# FC_board.net
KiCad netlist of a schematic drawn in Altium Designer
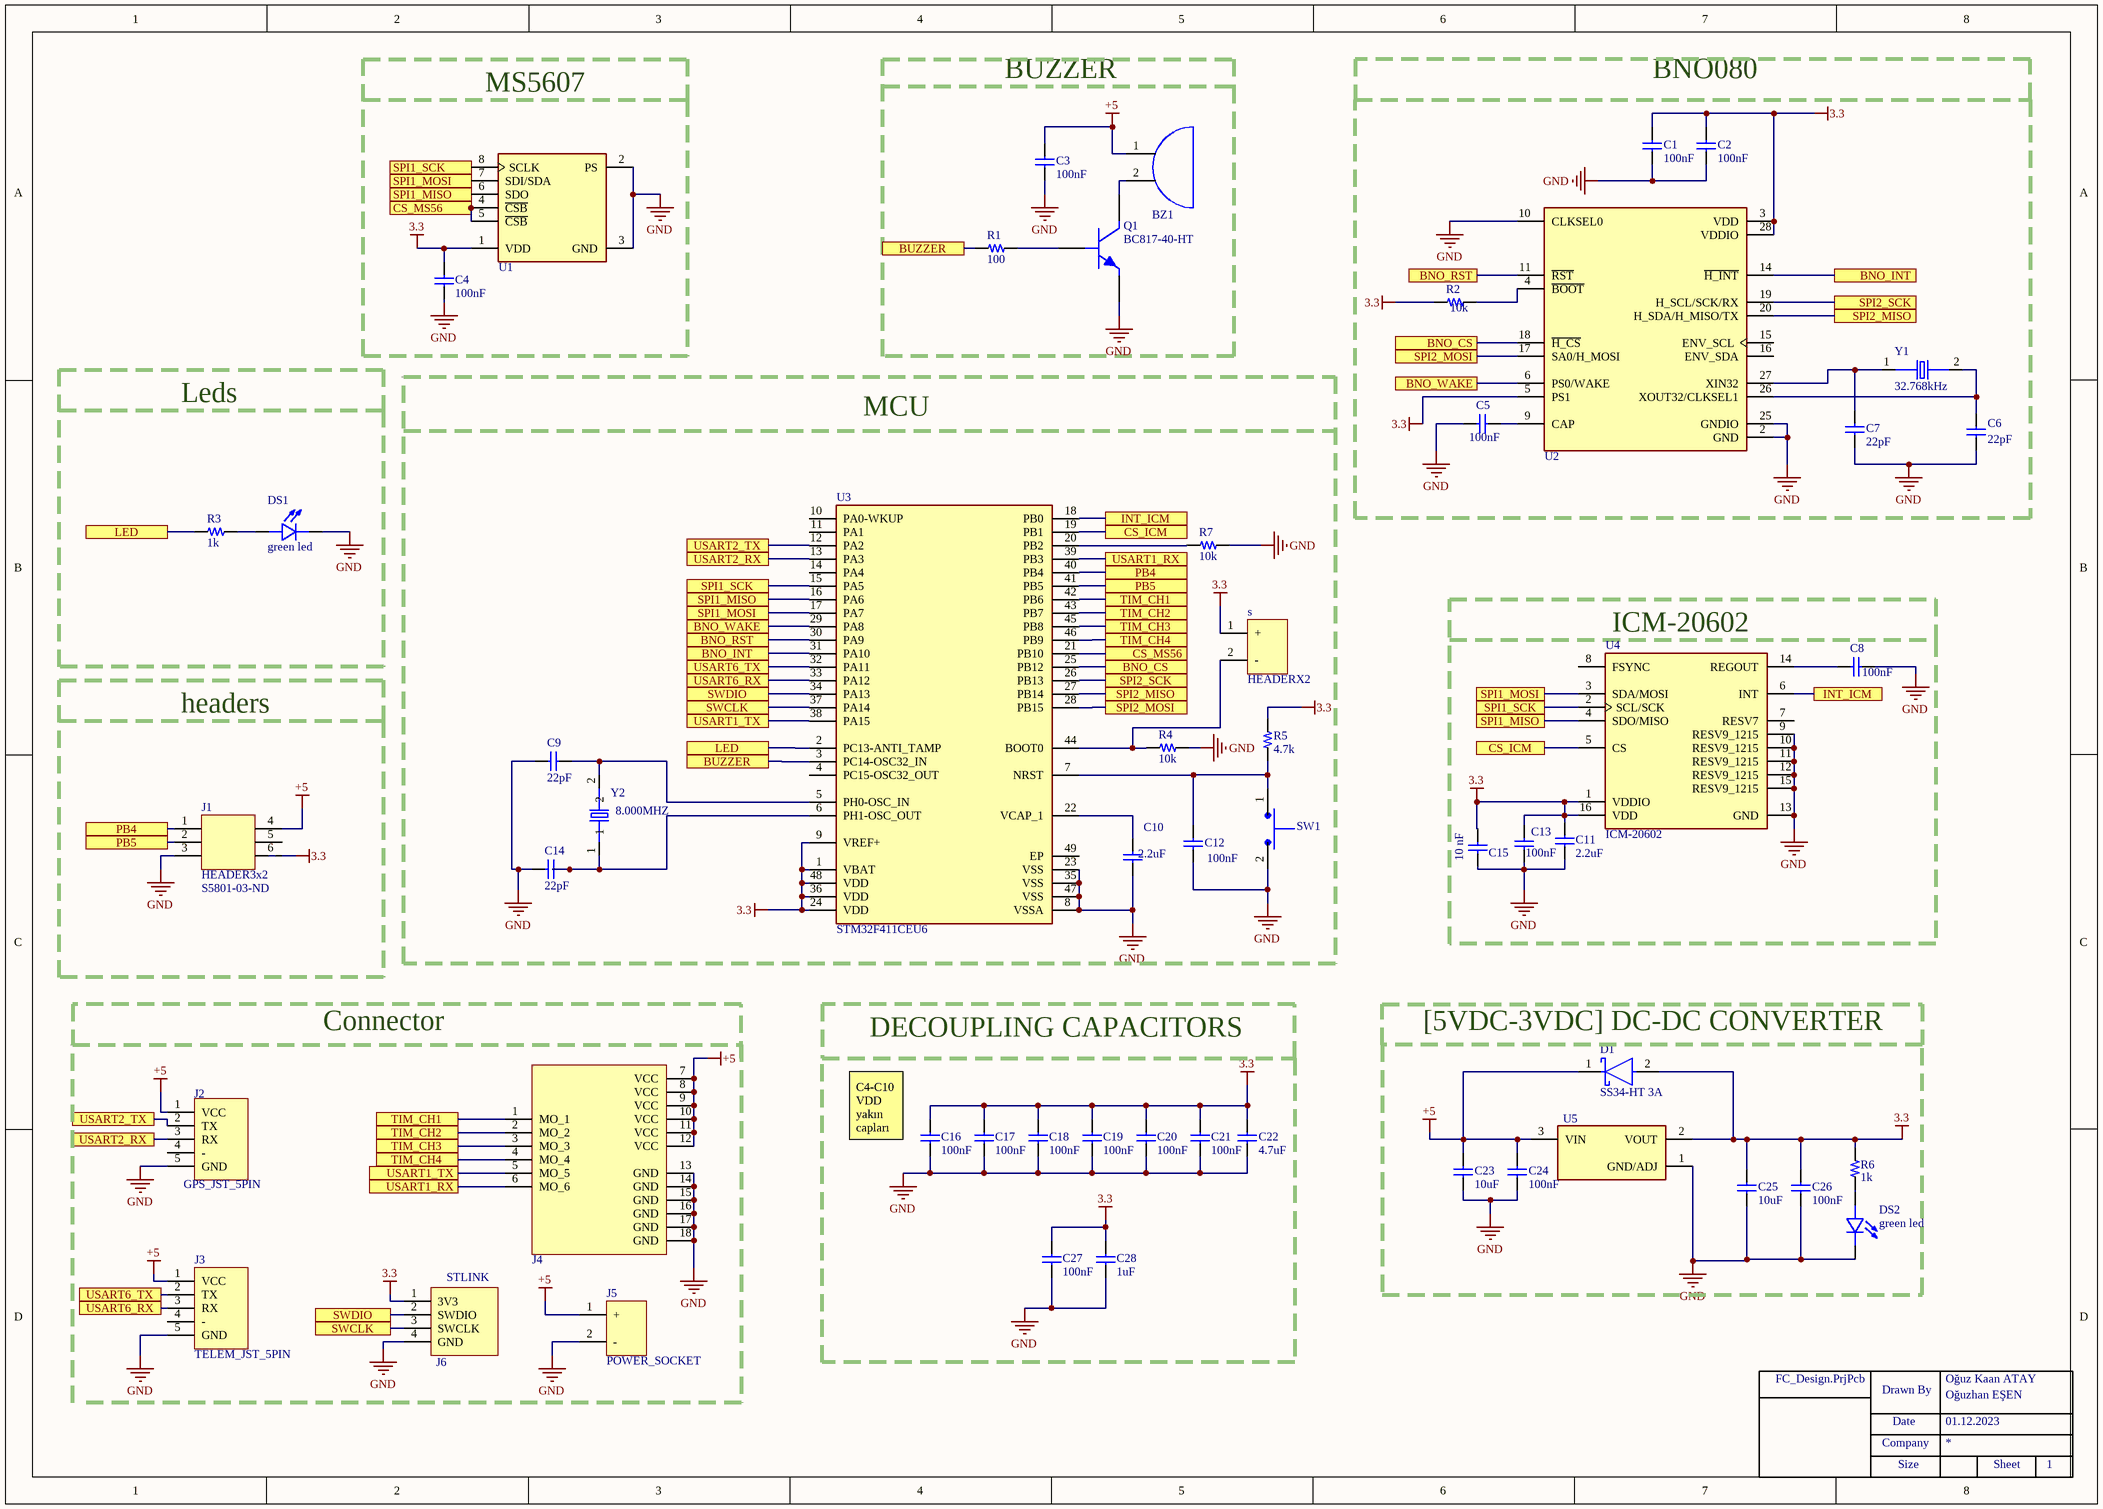
[diagram p0: FC_board.SchDoc]

(export (version "E")
  (design (tool "Eeschema 10.0.6"))
  (components
    (comp (ref "BZ1")
      (value "MB9650B05NP")
      (footprint "BUZZER")
      (libsource (lib "FC_Design_LIBINT") (part "MB9650B05NP"))
    )
    (comp (ref "C1")
      (value "CL21B105KBFNNNE")
      (footprint "CAP_0805")
      (description "CAP CER 1UF 50V X7R 0805")
      (fields
        (field (name "MANUFACTURER") "Samsung")
        (field (name "TOLERANCE") "10%")
        (field (name "CAPACITANCE") "100nF")
        (field (name "DESIGNED BY") "Oğuzhan EŞEN")
      )
      (libsource (lib "FC_Design_LIBINT") (part "CAP CER 1uF 0805"))
    )
    (comp (ref "C2")
      (value "CL21B105KBFNNNE")
      (footprint "CAP_0805")
      (description "CAP CER 1UF 50V X7R 0805")
      (fields
        (field (name "MANUFACTURER") "Samsung")
        (field (name "TOLERANCE") "10%")
        (field (name "CAPACITANCE") "100nF")
        (field (name "DESIGNED BY") "Oğuzhan EŞEN")
      )
      (libsource (lib "FC_Design_LIBINT") (part "CAP CER 1uF 0805"))
    )
    (comp (ref "C3")
      (value "CAP CER 100nF 0805")
      (footprint "CAP_0805")
      (description "CAP CER 100nF 50V X7R 0805")
      (fields
        (field (name "MANUFACTURER") "Samsung")
        (field (name "MANUFACTURER PART NUMBER") "CL21B105KBFNNNE")
        (field (name "CAPACITANCE") "100nF")
        (field (name "DESIGNED BY") "Oğuzhan EŞEN")
      )
      (libsource (lib "FC_Design_LIBINT") (part "CAP CER 100nF 0805"))
    )
    (comp (ref "C4")
      (value "CAP CER 100nF 0805")
      (footprint "CAP_0805")
      (description "CAP CER 100nF 50V X7R 0805")
      (fields
        (field (name "MANUFACTURER") "Samsung")
        (field (name "MANUFACTURER PART NUMBER") "CL21B105KBFNNNE")
        (field (name "CAPACITANCE") "100nF")
        (field (name "DESIGNED BY") "Oğuzhan EŞEN")
      )
      (libsource (lib "FC_Design_LIBINT") (part "CAP CER 100nF 0805"))
    )
    (comp (ref "C5")
      (value "CAP CER  0.1uF 0805")
      (footprint "CAP_0805")
      (description "CAP CER  0.1UF 50V X7R 0805")
      (fields
        (field (name "MANUFACTURER") "Samsung")
        (field (name "MANUFACTURER PART NUMBER") "CL21B105KBFNNNE")
        (field (name "CAPACITANCE") "100nF")
        (field (name "DESIGNED BY") "Oğuzhan EŞEN")
      )
      (libsource (lib "FC_Design_LIBINT") (part "CAP CER  0.1uF 0805"))
    )
    (comp (ref "C6")
      (value "CL21B105KBFNNNE")
      (footprint "CAP_0805")
      (description "CAP CER 22pF 50V X7R 0805")
      (fields
        (field (name "MANUFACTURER") "Samsung")
        (field (name "TOLERANCE") "10%")
        (field (name "CAPACITANCE") "22pF")
        (field (name "DESIGNED BY") "Oğuzhan EŞEN")
      )
      (libsource (lib "FC_Design_LIBINT") (part "CAP CER 22pF 0805"))
    )
    (comp (ref "C7")
      (value "CL21B105KBFNNNE")
      (footprint "CAP_0805")
      (description "CAP CER 22pF 50V X7R 0805")
      (fields
        (field (name "MANUFACTURER") "Samsung")
        (field (name "TOLERANCE") "10%")
        (field (name "CAPACITANCE") "22pF")
        (field (name "DESIGNED BY") "Oğuzhan EŞEN")
      )
      (libsource (lib "FC_Design_LIBINT") (part "CAP CER 22pF 0805"))
    )
    (comp (ref "C8")
      (value "CAP CER  0.1uF 0805")
      (footprint "CAP_0805")
      (description "CAP CER  0.1UF 50V X7R 0805")
      (fields
        (field (name "MANUFACTURER") "Samsung")
        (field (name "MANUFACTURER PART NUMBER") "CL21B105KBFNNNE")
        (field (name "CAPACITANCE") "100nF")
        (field (name "DESIGNED BY") "Oğuzhan EŞEN")
      )
      (libsource (lib "FC_Design_LIBINT") (part "CAP CER  0.1uF 0805"))
    )
    (comp (ref "C9")
      (value "CL21B105KBFNNNE")
      (footprint "CAP_0805")
      (description "CAP CER 22pF 50V X7R 0805")
      (fields
        (field (name "MANUFACTURER") "Samsung")
        (field (name "TOLERANCE") "10%")
        (field (name "CAPACITANCE") "22pF")
        (field (name "DESIGNED BY") "Oğuzhan EŞEN")
      )
      (libsource (lib "FC_Design_LIBINT") (part "CAP CER 22pF 0805"))
    )
    (comp (ref "C10")
      (value "CL21B105KBFNNNE")
      (footprint "CAP_0805")
      (description "CAP CER 22pF 50V X7R 0805")
      (fields
        (field (name "MANUFACTURER") "Samsung")
        (field (name "TOLERANCE") "10%")
        (field (name "CAPACITANCE") "2.2uF")
        (field (name "DESIGNED BY") "Oğuzhan EŞEN")
      )
      (libsource (lib "FC_Design_LIBINT") (part "CAP CER 22pF 0805"))
    )
    (comp (ref "C11")
      (value "CL21A475KAQNNNE")
      (footprint "CAP_0805")
      (description "CAP CER  2.2UF 50V X7R 0805")
      (fields
        (field (name "MANUFACTURER") "Samsung")
        (field (name "TOLERANCE") "10%")
        (field (name "CAPACITANCE") "2.2uF")
        (field (name "DESIGNED BY") "Oğuzhan EŞEN")
      )
      (libsource (lib "FC_Design_LIBINT") (part "CAP CER 2.2uF 0805_1"))
    )
    (comp (ref "C12")
      (value "~")
      (footprint "CAP_0805")
      (description "CAP CER  0.1UF 50V X7R 0805")
      (fields
        (field (name "MANUFACTURER") "Samsung")
        (field (name "MANUFACTURER PART NUMBER") "CL21B105KBFNNNE")
        (field (name "CAPACITANCE") "100nF")
        (field (name "DESIGNED BY") "Oğuzhan EŞEN")
      )
      (libsource (lib "FC_Design_LIBINT") (part "CAP CER  0.1uF 0805"))
    )
    (comp (ref "C13")
      (value "CAP CER  0.1uF 0805")
      (footprint "CAP_0805")
      (description "CAP CER  0.1UF 50V X7R 0805")
      (fields
        (field (name "MANUFACTURER") "Samsung")
        (field (name "MANUFACTURER PART NUMBER") "CL21B105KBFNNNE")
        (field (name "CAPACITANCE") "100nF")
        (field (name "DESIGNED BY") "Oğuzhan EŞEN")
      )
      (libsource (lib "FC_Design_LIBINT") (part "CAP CER  0.1uF 0805"))
    )
    (comp (ref "C14")
      (value "CL21B105KBFNNNE")
      (footprint "CAP_0805")
      (description "CAP CER 22pF 50V X7R 0805")
      (fields
        (field (name "MANUFACTURER") "Samsung")
        (field (name "TOLERANCE") "10%")
        (field (name "CAPACITANCE") "22pF")
        (field (name "DESIGNED BY") "Oğuzhan EŞEN")
      )
      (libsource (lib "FC_Design_LIBINT") (part "CAP CER 22pF 0805"))
    )
    (comp (ref "C15")
      (value "CAP CER 10nF 0805")
      (footprint "CAP_0805")
      (description "CAP CER  10nF 50V X7R 0805")
      (libsource (lib "FC_Design_LIBINT") (part "CAP CER 10nF 0805"))
    )
    (comp (ref "C16")
      (value "~")
      (footprint "CAP_0805")
      (description "CAP CER 100pF 50V X7R 0805")
      (fields
        (field (name "MANUFACTURER") "Samsung")
        (field (name "MANUFACTURER PART NUMBER") "CL21B105KBFNNNE")
        (field (name "CAPACITANCE") "100nF")
        (field (name "DESIGNED BY") "Oğuzhan EŞEN")
      )
      (libsource (lib "FC_Design_LIBINT") (part "CAP CER 100pF 0805"))
    )
    (comp (ref "C17")
      (value "~")
      (footprint "CAP_0805")
      (description "CAP CER 100pF 50V X7R 0805")
      (fields
        (field (name "MANUFACTURER") "Samsung")
        (field (name "MANUFACTURER PART NUMBER") "CL21B105KBFNNNE")
        (field (name "CAPACITANCE") "100nF")
        (field (name "DESIGNED BY") "Oğuzhan EŞEN")
      )
      (libsource (lib "FC_Design_LIBINT") (part "CAP CER 100pF 0805"))
    )
    (comp (ref "C18")
      (value "~")
      (footprint "CAP_0805")
      (description "CAP CER 100pF 50V X7R 0805")
      (fields
        (field (name "MANUFACTURER") "Samsung")
        (field (name "MANUFACTURER PART NUMBER") "CL21B105KBFNNNE")
        (field (name "CAPACITANCE") "100nF")
        (field (name "DESIGNED BY") "Oğuzhan EŞEN")
      )
      (libsource (lib "FC_Design_LIBINT") (part "CAP CER 100pF 0805"))
    )
    (comp (ref "C19")
      (value "~")
      (footprint "CAP_0805")
      (description "CAP CER 100pF 50V X7R 0805")
      (fields
        (field (name "MANUFACTURER") "Samsung")
        (field (name "MANUFACTURER PART NUMBER") "CL21B105KBFNNNE")
        (field (name "CAPACITANCE") "100nF")
        (field (name "DESIGNED BY") "Oğuzhan EŞEN")
      )
      (libsource (lib "FC_Design_LIBINT") (part "CAP CER 100pF 0805"))
    )
    (comp (ref "C20")
      (value "~")
      (footprint "CAP_0805")
      (description "CAP CER 100pF 50V X7R 0805")
      (fields
        (field (name "MANUFACTURER") "Samsung")
        (field (name "MANUFACTURER PART NUMBER") "CL21B105KBFNNNE")
        (field (name "CAPACITANCE") "100nF")
        (field (name "DESIGNED BY") "Oğuzhan EŞEN")
      )
      (libsource (lib "FC_Design_LIBINT") (part "CAP CER 100pF 0805"))
    )
    (comp (ref "C21")
      (value "~")
      (footprint "CAP_0805")
      (description "CAP CER 100pF 50V X7R 0805")
      (fields
        (field (name "MANUFACTURER") "Samsung")
        (field (name "MANUFACTURER PART NUMBER") "CL21B105KBFNNNE")
        (field (name "CAPACITANCE") "100nF")
        (field (name "DESIGNED BY") "Oğuzhan EŞEN")
      )
      (libsource (lib "FC_Design_LIBINT") (part "CAP CER 100pF 0805"))
    )
    (comp (ref "C22")
      (value "~")
      (footprint "CAP_0805")
      (description "CAP CER 4.7UF 25V X5R 0805")
      (fields
        (field (name "MANUFACTURER") "Samsung")
        (field (name "MANUFACTURER PART NUMBER") "CL21A475KAQNNNE")
        (field (name "CAPACITANCE") "4.7uF")
        (field (name "DESIGNED BY") "Oğuzhan EŞEN")
      )
      (libsource (lib "FC_Design_LIBINT") (part "CAP CER 4,7uF 0805"))
    )
    (comp (ref "C23")
      (value "CAP CER 10uF 0805")
      (footprint "CAP_0805")
      (description "CAP CER 10uF 25V X5R 0805")
      (fields
        (field (name "MANUFACTURER") "Samsung")
        (field (name "MANUFACTURER PART NUMBER") "CL21A475KAQNNNE")
        (field (name "CAPACITANCE") "10uF")
        (field (name "DESIGNED BY") "Oğuzhan EŞEN")
      )
      (libsource (lib "FC_Design_LIBINT") (part "CAP CER 10uF 0805"))
    )
    (comp (ref "C24")
      (value "~")
      (footprint "CAP_0805")
      (description "CAP CER 100nF 50V X7R 0805")
      (fields
        (field (name "MANUFACTURER") "Samsung")
        (field (name "MANUFACTURER PART NUMBER") "CL21B105KBFNNNE")
        (field (name "CAPACITANCE") "100nF")
        (field (name "DESIGNED BY") "Oğuzhan EŞEN")
      )
      (libsource (lib "FC_Design_LIBINT") (part "CAP CER 100nF 0805"))
    )
    (comp (ref "C25")
      (value "CAP CER 10uF 0805")
      (footprint "CAP_0805")
      (description "CAP CER 10uF 25V X5R 0805")
      (fields
        (field (name "MANUFACTURER") "Samsung")
        (field (name "MANUFACTURER PART NUMBER") "CL21A475KAQNNNE")
        (field (name "CAPACITANCE") "10uF")
        (field (name "DESIGNED BY") "Oğuzhan EŞEN")
      )
      (libsource (lib "FC_Design_LIBINT") (part "CAP CER 10uF 0805"))
    )
    (comp (ref "C26")
      (value "~")
      (footprint "CAP_0805")
      (description "CAP CER 100nF 50V X7R 0805")
      (fields
        (field (name "MANUFACTURER") "Samsung")
        (field (name "MANUFACTURER PART NUMBER") "CL21B105KBFNNNE")
        (field (name "CAPACITANCE") "100nF")
        (field (name "DESIGNED BY") "Oğuzhan EŞEN")
      )
      (libsource (lib "FC_Design_LIBINT") (part "CAP CER 100nF 0805"))
    )
    (comp (ref "C27")
      (value "~")
      (footprint "CAP_0805")
      (description "CAP CER 100nF 50V X7R 0805")
      (fields
        (field (name "MANUFACTURER") "Samsung")
        (field (name "MANUFACTURER PART NUMBER") "CL21B105KBFNNNE")
        (field (name "CAPACITANCE") "100nF")
        (field (name "DESIGNED BY") "Oğuzhan EŞEN")
      )
      (libsource (lib "FC_Design_LIBINT") (part "CAP CER 100nF 0805"))
    )
    (comp (ref "C28")
      (value "~")
      (footprint "CAP_0805")
      (description "CAP CER 1UF 50V X7R 0805")
      (fields
        (field (name "MANUFACTURER") "Samsung")
        (field (name "MANUFACTURER PART NUMBER") "CL21B105KBFNNNE")
        (field (name "CAPACITANCE") "1uF")
        (field (name "DESIGNED BY") "Oğuzhan EŞEN")
      )
      (libsource (lib "FC_Design_LIBINT") (part "CAP CER 1uF 0805"))
    )
    (comp (ref "D1")
      (value "SS34-HT 3A")
      (footprint "FP-95402-MFG")
      (description "DIODE SCHOTTKY 40V 3A DIODE SCHOTTKY 40V 3A DO214AB")
      (fields (field (name "MANUFACTURER") "Vishay") (field (name "MANUFACTURER PART NUMBER") "SS34-E3/57T"))
      (libsource (lib "Altium Content Vault") (part "1d6ec82d83fb6aee721767c19dac4b9"))
    )
    (comp (ref "DS1")
      (value "green led")
      (footprint "GREEEN_LED_0805")
      (libsource (lib "FC_Design_LIBINT") (part "green led"))
    )
    (comp (ref "DS2")
      (value "green led")
      (footprint "GREEEN_LED_0805")
      (libsource (lib "") (part "green led_1"))
    )
    (comp (ref "J1")
      (value "HEADER3x2")
      (footprint "HEADER3x2")
      (description "CONN HEADER 2MM DUAL STR 6POS")
      (fields
        (field (name "MANUFACTURER") "Sullins")
        (field (name "MANUFACTURER PART NUMBER") "NRPN032PAEN-RC")
        (field (name "SUPPLIER PART NUMBER 1") "S5801-03-ND")
        (field (name "DESIGNED BY") "Oğuzhan EŞEN")
      )
      (libsource (lib "Arduino") (part "HEADER3x2"))
    )
    (comp (ref "J2")
      (value "GPS_JST_5PIN")
      (footprint "JST_5PIN_125")
      (libsource (lib "FC_Design_LIBINT") (part "GPS_JST_5PIN"))
    )
    (comp (ref "J3")
      (value "TELEM_JST_5PIN")
      (footprint "JST_5PIN_125")
      (libsource (lib "FC_Design_LIBINT") (part "TELEM_JST_5PIN"))
    )
    (comp (ref "J4")
      (value "Motor_Outputs")
      (footprint "MOTORS")
      (libsource (lib "FC_Design_LIBINT") (part "Motor_Outputs"))
    )
    (comp (ref "J5")
      (value "POWER_SOCKET")
      (footprint "JST_2PIN_2.54")
      (libsource (lib "FC_Design_LIBINT") (part "POWER_SOCKET"))
    )
    (comp (ref "J6")
      (value "STLINK")
      (footprint "HEADER_4_MALE")
      (libsource (lib "FC_Design_LIBINT") (part "RECIVER"))
    )
    (comp (ref "Q1")
      (value "BC817-40-HT")
      (footprint "SOT23")
      (description "npn transistor")
      (libsource (lib "FC_Design_LIBINT") (part "BC817-40-HT"))
    )
    (comp (ref "R1")
      (value "100")
      (footprint "RES_0805")
      (description "910 Ohms Â±1% 0.125W, 1/8W Chip Resistor 0805 (2012 Metric) Moisture Resistant Thick Film")
      (fields (field (name "MF") "Yageo") (field (name "MP") "RC0805FR-07910RL"))
      (libsource (lib "FC_Design_LIBINT") (part "RESISTOR_0805"))
    )
    (comp (ref "R2")
      (value "10k")
      (footprint "RES_0805")
      (description "910 Ohms Â±1% 0.125W, 1/8W Chip Resistor 0805 (2012 Metric) Moisture Resistant Thick Film")
      (fields (field (name "MF") "Yageo") (field (name "MP") "RC0805FR-07910RL"))
      (libsource (lib "FC_Design_LIBINT") (part "RESISTOR_0805"))
    )
    (comp (ref "R3")
      (value "1k")
      (footprint "RES_0805")
      (description "910 Ohms Â±1% 0.125W, 1/8W Chip Resistor 0805 (2012 Metric) Moisture Resistant Thick Film")
      (fields (field (name "MF") "Yageo") (field (name "MP") "RC0805FR-07910RL"))
      (libsource (lib "FC_Design_LIBINT") (part "RESISTOR_0805"))
    )
    (comp (ref "R4")
      (value "10k")
      (footprint "RES_0805")
      (description "910 Ohms Â±1% 0.125W, 1/8W Chip Resistor 0805 (2012 Metric) Moisture Resistant Thick Film")
      (fields (field (name "MF") "Yageo") (field (name "MP") "RC0805FR-07910RL"))
      (libsource (lib "FC_Design_LIBINT") (part "RESISTOR_0805"))
    )
    (comp (ref "R5")
      (value "4.7k")
      (footprint "RES_0805")
      (description "910 Ohms Â±1% 0.125W, 1/8W Chip Resistor 0805 (2012 Metric) Moisture Resistant Thick Film")
      (fields (field (name "MF") "Yageo") (field (name "MP") "RC0805FR-07910RL"))
      (libsource (lib "FC_Design_LIBINT") (part "RESISTOR_0805"))
    )
    (comp (ref "R6")
      (value "1k")
      (footprint "RES_0805")
      (description "910 Ohms Â±1% 0.125W, 1/8W Chip Resistor 0805 (2012 Metric) Moisture Resistant Thick Film")
      (fields (field (name "MF") "Yageo") (field (name "MP") "RC0805FR-07910RL"))
      (libsource (lib "FC_Design_LIBINT") (part "RESISTOR_0805"))
    )
    (comp (ref "R7")
      (value "10k")
      (footprint "RES_0805")
      (description "910 Ohms Â±1% 0.125W, 1/8W Chip Resistor 0805 (2012 Metric) Moisture Resistant Thick Film")
      (fields (field (name "MF") "Yageo") (field (name "MP") "RC0805FR-07910RL"))
      (libsource (lib "FC_Design_LIBINT") (part "RESISTOR_0805"))
    )
    (comp (ref "s")
      (value "HEADERX2")
      (footprint "PIN_2.54")
      (libsource (lib "FC_Design_LIBINT") (part "HEADERX2"))
    )
    (comp (ref "SW1")
      (value "Switch Tactile")
      (footprint "BUTTON")
      (description "Switch Tactile N.O. SPST Rectangular Button J-Bend 0.02A 15VDC 5N SMD Embossed Tape and Reel")
      (fields
        (field (name "MANUFACTURER") "Panasonic")
        (field (name "MANUFACTURER PART NUMBER") "EVQP9H02W")
        (field (name "DESIGNED BY") "Oğuzhan EŞEN")
      )
      (libsource (lib "Integrated_LibraryFCLibPkg") (part "button"))
    )
    (comp (ref "U1")
      (value "MS560702BA03-50")
      (footprint "SON125P300X500X100-8N")
      (description "MS5607-02BA03 Series 3 V 1 to 120 kPa Absolute Barometric Pressure Sensor")
      (fields (field (name "MF") "TE Connectivity"))
      (libsource (lib "FC_Design_LIBINT") (part "MS560702BA03-50"))
    )
    (comp (ref "U2")
      (value "BNO080")
      (footprint "BNO080")
      (description "Accelerometer, Gyroscope, Magnetometer, 9 Axis Sensor IÂ²C, SPI, UART Output")
      (fields
        (field (name "MF") "Hillcrest Laboratories,")
        (field (name "DIGI-KEY_PART_NUMBER") "1888-1000-1-ND")
      )
      (libsource (lib "FC_Design_LIBINT") (part "BNO080"))
    )
    (comp (ref "U3")
      (value "STM32F411CEU6")
      (footprint "QFN50P700X700X60-49N")
      (libsource (lib "FC_Design_LIBINT") (part "STM32F411CEU6"))
    )
    (comp (ref "U4")
      (value "ICM-20602")
      (footprint "PQFN50P300X300X80-16N")
      (libsource (lib "FC_Design_LIB") (part "ICM-20602"))
    )
    (comp (ref "U5")
      (value "LDO Voltage Regulators 1A, 3.3V")
      (footprint "SOT229P700X180-4N")
      (libsource (lib "FC_Design_LIBINT") (part "AMS1117"))
    )
    (comp (ref "Y1")
      (value "32.768kHz")
      (footprint "CRYSTAL_32_15")
      (description "32.768kHz Â±20ppm Crystal 7pF 70 kOhms 2-SMD, No Lead")
      (fields (field (name "MP") "FC-135") (field (name "MF") "EPSON"))
      (libsource (lib "FC_Design_LIBINT") (part "FC-135 BNO"))
    )
    (comp (ref "Y2")
      (value "8.000MHZ")
      (footprint "ABM3-8.000MHZ-D2Y-T")
      (description "ABM3-8.000MHZ-D2Y-T")
      (libsource (lib "FC_Design_LIBINT") (part "STM_CRYSTAL"))
    )
  )
  (nets
    (net (code "1") (name "+5") (class "Default")
      (node (ref "BZ1") (pin "1") (pinfunction "GND_1") (pintype "passive"))
      (node (ref "C23") (pin "2") (pinfunction "2_2") (pintype "passive"))
      (node (ref "C24") (pin "2") (pinfunction "2_2") (pintype "passive"))
      (node (ref "C3") (pin "2") (pinfunction "2_2") (pintype "passive"))
      (node (ref "D1") (pin "1") (pinfunction "C_1") (pintype "passive"))
      (node (ref "J1") (pin "4") (pinfunction "4_4") (pintype "passive"))
      (node (ref "J2") (pin "1") (pinfunction "VCC_1") (pintype "passive"))
      (node (ref "J3") (pin "1") (pinfunction "VCC_1") (pintype "passive"))
      (node (ref "J4") (pin "10") (pinfunction "VCC_10") (pintype "passive"))
      (node (ref "J4") (pin "11") (pinfunction "VCC_11") (pintype "passive"))
      (node (ref "J4") (pin "12") (pinfunction "VCC_12") (pintype "passive"))
      (node (ref "J4") (pin "7") (pinfunction "VCC_7") (pintype "passive"))
      (node (ref "J4") (pin "8") (pinfunction "VCC_8") (pintype "passive"))
      (node (ref "J4") (pin "9") (pinfunction "VCC_9") (pintype "passive"))
      (node (ref "J5") (pin "1") (pinfunction "+_1") (pintype "passive"))
      (node (ref "U5") (pin "3") (pinfunction "VIN_3") (pintype "passive"))
    )
    (net (code "2") (name "/BNO_CS") (class "Default")
      (node (ref "U2") (pin "18") (pinfunction "~{H_CS}_18") (pintype "passive"))
      (node (ref "U3") (pin "25") (pinfunction "PB12_25") (pintype "passive"))
    )
    (net (code "3") (name "/BNO_INT") (class "Default")
      (node (ref "U2") (pin "14") (pinfunction "~{H_INT}_14") (pintype "passive"))
      (node (ref "U3") (pin "31") (pinfunction "PA10_31") (pintype "passive"))
    )
    (net (code "4") (name "/BNO_RST") (class "Default")
      (node (ref "U2") (pin "11") (pinfunction "~{RST}_11") (pintype "passive"))
      (node (ref "U3") (pin "30") (pinfunction "PA9_30") (pintype "passive"))
    )
    (net (code "5") (name "/BNO_WAKE") (class "Default")
      (node (ref "U2") (pin "6") (pinfunction "PS0/WAKE_6") (pintype "passive"))
      (node (ref "U3") (pin "29") (pinfunction "PA8_29") (pintype "passive"))
    )
    (net (code "6") (name "/BUZZER") (class "Default")
      (node (ref "R1") (pin "2") (pinfunction "2_2") (pintype "passive"))
      (node (ref "U3") (pin "3") (pinfunction "PC14-OSC32_IN_3") (pintype "passive"))
    )
    (net (code "7") (name "/CS_ICM") (class "Default")
      (node (ref "U3") (pin "19") (pinfunction "PB1_19") (pintype "passive"))
      (node (ref "U4") (pin "5") (pinfunction "CS_5") (pintype "passive"))
    )
    (net (code "8") (name "/CS_MS56") (class "Default")
      (node (ref "U1") (pin "4") (pinfunction "~{CSB}_4") (pintype "passive"))
      (node (ref "U1") (pin "5") (pinfunction "~{CSB}_5") (pintype "passive"))
      (node (ref "U3") (pin "21") (pinfunction "PB10_21") (pintype "passive"))
    )
    (net (code "9") (name "/INT_ICM") (class "Default")
      (node (ref "U3") (pin "18") (pinfunction "PB0_18") (pintype "passive"))
      (node (ref "U4") (pin "6") (pinfunction "INT_6") (pintype "passive"))
    )
    (net (code "10") (name "/LED") (class "Default")
      (node (ref "R3") (pin "2") (pinfunction "2_2") (pintype "passive"))
      (node (ref "U3") (pin "2") (pinfunction "PC13-ANTI_TAMP_2") (pintype "passive"))
    )
    (net (code "11") (name "/PB4") (class "Default")
      (node (ref "J1") (pin "1") (pinfunction "1_1") (pintype "passive"))
      (node (ref "U3") (pin "40") (pinfunction "PB4_40") (pintype "passive"))
    )
    (net (code "12") (name "/PB5") (class "Default")
      (node (ref "J1") (pin "2") (pinfunction "2_2") (pintype "passive"))
      (node (ref "U3") (pin "41") (pinfunction "PB5_41") (pintype "passive"))
    )
    (net (code "13") (name "/SPI1_MISO") (class "Default")
      (node (ref "U1") (pin "6") (pinfunction "SDO_6") (pintype "passive"))
      (node (ref "U3") (pin "16") (pinfunction "PA6_16") (pintype "passive"))
      (node (ref "U4") (pin "4") (pinfunction "SDO/MISO_4") (pintype "passive"))
    )
    (net (code "14") (name "/SPI1_MOSI") (class "Default")
      (node (ref "U1") (pin "7") (pinfunction "SDI/SDA_7") (pintype "passive"))
      (node (ref "U3") (pin "17") (pinfunction "PA7_17") (pintype "passive"))
      (node (ref "U4") (pin "3") (pinfunction "SDA/MOSI_3") (pintype "passive"))
    )
    (net (code "15") (name "/SPI1_SCK") (class "Default")
      (node (ref "U1") (pin "8") (pinfunction "SCLK_8") (pintype "passive"))
      (node (ref "U3") (pin "15") (pinfunction "PA5_15") (pintype "passive"))
      (node (ref "U4") (pin "2") (pinfunction "SCL/SCK_2") (pintype "passive"))
    )
    (net (code "16") (name "/SPI2_MISO") (class "Default")
      (node (ref "U2") (pin "20") (pinfunction "H_SDA/H_MISO/TX_20") (pintype "passive"))
      (node (ref "U3") (pin "27") (pinfunction "PB14_27") (pintype "passive"))
    )
    (net (code "17") (name "/SPI2_MOSI") (class "Default")
      (node (ref "U2") (pin "17") (pinfunction "SA0/H_MOSI_17") (pintype "passive"))
      (node (ref "U3") (pin "28") (pinfunction "PB15_28") (pintype "passive"))
    )
    (net (code "18") (name "/SPI2_SCK") (class "Default")
      (node (ref "U2") (pin "19") (pinfunction "H_SCL/SCK/RX_19") (pintype "passive"))
      (node (ref "U3") (pin "26") (pinfunction "PB13_26") (pintype "passive"))
    )
    (net (code "19") (name "/SWCLK") (class "Default")
      (node (ref "J6") (pin "3") (pinfunction "SWCLK_3") (pintype "passive"))
      (node (ref "U3") (pin "37") (pinfunction "PA14_37") (pintype "passive"))
    )
    (net (code "20") (name "/SWDIO") (class "Default")
      (node (ref "J6") (pin "2") (pinfunction "SWDIO_2") (pintype "passive"))
      (node (ref "U3") (pin "34") (pinfunction "PA13_34") (pintype "passive"))
    )
    (net (code "21") (name "/TIM_CH1") (class "Default")
      (node (ref "J4") (pin "1") (pinfunction "MO_1_1") (pintype "passive"))
      (node (ref "U3") (pin "42") (pinfunction "PB6_42") (pintype "passive"))
    )
    (net (code "22") (name "/TIM_CH2") (class "Default")
      (node (ref "J4") (pin "2") (pinfunction "MO_2_2") (pintype "passive"))
      (node (ref "U3") (pin "43") (pinfunction "PB7_43") (pintype "passive"))
    )
    (net (code "23") (name "/TIM_CH3") (class "Default")
      (node (ref "J4") (pin "3") (pinfunction "MO_3_3") (pintype "passive"))
      (node (ref "U3") (pin "45") (pinfunction "PB8_45") (pintype "passive"))
    )
    (net (code "24") (name "/TIM_CH4") (class "Default")
      (node (ref "J4") (pin "4") (pinfunction "MO_4_4") (pintype "passive"))
      (node (ref "U3") (pin "46") (pinfunction "PB9_46") (pintype "passive"))
    )
    (net (code "25") (name "/USART1_RX") (class "Default")
      (node (ref "J4") (pin "6") (pinfunction "MO_6_6") (pintype "passive"))
      (node (ref "U3") (pin "39") (pinfunction "PB3_39") (pintype "passive"))
    )
    (net (code "26") (name "/USART1_TX") (class "Default")
      (node (ref "J4") (pin "5") (pinfunction "MO_5_5") (pintype "passive"))
      (node (ref "U3") (pin "38") (pinfunction "PA15_38") (pintype "passive"))
    )
    (net (code "27") (name "/USART2_RX") (class "Default")
      (node (ref "J2") (pin "3") (pinfunction "RX_3") (pintype "passive"))
      (node (ref "U3") (pin "13") (pinfunction "PA3_13") (pintype "passive"))
    )
    (net (code "28") (name "/USART2_TX") (class "Default")
      (node (ref "J2") (pin "2") (pinfunction "TX_2") (pintype "passive"))
      (node (ref "U3") (pin "12") (pinfunction "PA2_12") (pintype "passive"))
    )
    (net (code "29") (name "/USART6_RX") (class "Default")
      (node (ref "J3") (pin "3") (pinfunction "RX_3") (pintype "passive"))
      (node (ref "U3") (pin "33") (pinfunction "PA12_33") (pintype "passive"))
    )
    (net (code "30") (name "/USART6_TX") (class "Default")
      (node (ref "J3") (pin "2") (pinfunction "TX_2") (pintype "passive"))
      (node (ref "U3") (pin "32") (pinfunction "PA11_32") (pintype "passive"))
    )
    (net (code "31") (name "3.3") (class "Default")
      (node (ref "C1") (pin "2") (pinfunction "2_2") (pintype "passive"))
      (node (ref "C11") (pin "2") (pinfunction "2_2") (pintype "passive"))
      (node (ref "C13") (pin "1") (pinfunction "1_1") (pintype "passive"))
      (node (ref "C15") (pin "2") (pinfunction "2_2") (pintype "passive"))
      (node (ref "C16") (pin "2") (pinfunction "2_2") (pintype "passive"))
      (node (ref "C17") (pin "2") (pinfunction "2_2") (pintype "passive"))
      (node (ref "C18") (pin "2") (pinfunction "2_2") (pintype "passive"))
      (node (ref "C19") (pin "2") (pinfunction "2_2") (pintype "passive"))
      (node (ref "C2") (pin "2") (pinfunction "2_2") (pintype "passive"))
      (node (ref "C20") (pin "2") (pinfunction "2_2") (pintype "passive"))
      (node (ref "C21") (pin "2") (pinfunction "2_2") (pintype "passive"))
      (node (ref "C22") (pin "2") (pinfunction "2_2") (pintype "passive"))
      (node (ref "C25") (pin "2") (pinfunction "2_2") (pintype "passive"))
      (node (ref "C26") (pin "2") (pinfunction "2_2") (pintype "passive"))
      (node (ref "C27") (pin "2") (pinfunction "2_2") (pintype "passive"))
      (node (ref "C28") (pin "2") (pinfunction "2_2") (pintype "passive"))
      (node (ref "C4") (pin "2") (pinfunction "2_2") (pintype "passive"))
      (node (ref "D1") (pin "2") (pinfunction "A_2") (pintype "passive"))
      (node (ref "J1") (pin "6") (pinfunction "6_6") (pintype "passive"))
      (node (ref "J6") (pin "1") (pinfunction "3V3_1") (pintype "passive"))
      (node (ref "R2") (pin "2") (pinfunction "2_2") (pintype "passive"))
      (node (ref "R5") (pin "1") (pinfunction "1_1") (pintype "passive"))
      (node (ref "R6") (pin "1") (pinfunction "1_1") (pintype "passive"))
      (node (ref "U1") (pin "1") (pinfunction "VDD_1") (pintype "passive"))
      (node (ref "U2") (pin "28") (pinfunction "VDDIO_28") (pintype "power_in"))
      (node (ref "U2") (pin "3") (pinfunction "VDD_3") (pintype "power_in"))
      (node (ref "U2") (pin "5") (pinfunction "PS1_5") (pintype "passive"))
      (node (ref "U3") (pin "1") (pinfunction "VBAT_1") (pintype "passive"))
      (node (ref "U3") (pin "24") (pinfunction "VDD_24") (pintype "passive"))
      (node (ref "U3") (pin "36") (pinfunction "VDD_36") (pintype "passive"))
      (node (ref "U3") (pin "48") (pinfunction "VDD_48") (pintype "passive"))
      (node (ref "U3") (pin "9") (pinfunction "VREF+_9") (pintype "passive"))
      (node (ref "U4") (pin "1") (pinfunction "VDDIO_1") (pintype "passive"))
      (node (ref "U4") (pin "16") (pinfunction "VDD_16") (pintype "passive"))
      (node (ref "U5") (pin "2") (pinfunction "VOUT_2") (pintype "passive"))
      (node (ref "s") (pin "1") (pinfunction "+_1") (pintype "passive"))
    )
    (net (code "32") (name "GND") (class "Default")
      (node (ref "C1") (pin "1") (pinfunction "1_1") (pintype "passive"))
      (node (ref "C10") (pin "1") (pinfunction "1_1") (pintype "passive"))
      (node (ref "C11") (pin "1") (pinfunction "1_1") (pintype "passive"))
      (node (ref "C12") (pin "1") (pinfunction "1_1") (pintype "passive"))
      (node (ref "C13") (pin "2") (pinfunction "2_2") (pintype "passive"))
      (node (ref "C14") (pin "1") (pinfunction "1_1") (pintype "passive"))
      (node (ref "C15") (pin "1") (pinfunction "1_1") (pintype "passive"))
      (node (ref "C16") (pin "1") (pinfunction "1_1") (pintype "passive"))
      (node (ref "C17") (pin "1") (pinfunction "1_1") (pintype "passive"))
      (node (ref "C18") (pin "1") (pinfunction "1_1") (pintype "passive"))
      (node (ref "C19") (pin "1") (pinfunction "1_1") (pintype "passive"))
      (node (ref "C2") (pin "1") (pinfunction "1_1") (pintype "passive"))
      (node (ref "C20") (pin "1") (pinfunction "1_1") (pintype "passive"))
      (node (ref "C21") (pin "1") (pinfunction "1_1") (pintype "passive"))
      (node (ref "C22") (pin "1") (pinfunction "1_1") (pintype "passive"))
      (node (ref "C23") (pin "1") (pinfunction "1_1") (pintype "passive"))
      (node (ref "C24") (pin "1") (pinfunction "1_1") (pintype "passive"))
      (node (ref "C25") (pin "1") (pinfunction "1_1") (pintype "passive"))
      (node (ref "C26") (pin "1") (pinfunction "1_1") (pintype "passive"))
      (node (ref "C27") (pin "1") (pinfunction "1_1") (pintype "passive"))
      (node (ref "C28") (pin "1") (pinfunction "1_1") (pintype "passive"))
      (node (ref "C3") (pin "1") (pinfunction "1_1") (pintype "passive"))
      (node (ref "C4") (pin "1") (pinfunction "1_1") (pintype "passive"))
      (node (ref "C5") (pin "1") (pinfunction "1_1") (pintype "passive"))
      (node (ref "C6") (pin "1") (pinfunction "1_1") (pintype "passive"))
      (node (ref "C7") (pin "1") (pinfunction "1_1") (pintype "passive"))
      (node (ref "C8") (pin "2") (pinfunction "2_2") (pintype "passive"))
      (node (ref "C9") (pin "1") (pinfunction "1_1") (pintype "passive"))
      (node (ref "DS1") (pin "2") (pinfunction "2_2") (pintype "passive"))
      (node (ref "DS2") (pin "2") (pinfunction "2_2") (pintype "passive"))
      (node (ref "J1") (pin "3") (pinfunction "3_3") (pintype "passive"))
      (node (ref "J2") (pin "5") (pinfunction "GND_5") (pintype "passive"))
      (node (ref "J3") (pin "5") (pinfunction "GND_5") (pintype "passive"))
      (node (ref "J4") (pin "13") (pinfunction "GND_13") (pintype "passive"))
      (node (ref "J4") (pin "14") (pinfunction "GND_14") (pintype "passive"))
      (node (ref "J4") (pin "15") (pinfunction "GND_15") (pintype "passive"))
      (node (ref "J4") (pin "16") (pinfunction "GND_16") (pintype "passive"))
      (node (ref "J4") (pin "17") (pinfunction "GND_17") (pintype "passive"))
      (node (ref "J4") (pin "18") (pinfunction "GND_18") (pintype "passive"))
      (node (ref "J5") (pin "2") (pinfunction "-_2") (pintype "passive"))
      (node (ref "J6") (pin "4") (pinfunction "GND_4") (pintype "passive"))
      (node (ref "Q1") (pin "2") (pinfunction "E_2") (pintype "passive"))
      (node (ref "R4") (pin "1") (pinfunction "1_1") (pintype "passive"))
      (node (ref "R7") (pin "1") (pinfunction "1_1") (pintype "passive"))
      (node (ref "SW1") (pin "2") (pinfunction "2_2") (pintype "passive"))
      (node (ref "U1") (pin "2") (pinfunction "PS_2") (pintype "passive"))
      (node (ref "U1") (pin "3") (pinfunction "GND_3") (pintype "passive"))
      (node (ref "U2") (pin "10") (pinfunction "CLKSEL0_10") (pintype "passive"))
      (node (ref "U2") (pin "2") (pinfunction "GND_2") (pintype "power_in"))
      (node (ref "U2") (pin "25") (pinfunction "GNDIO_25") (pintype "power_in"))
      (node (ref "U3") (pin "23") (pinfunction "VSS_23") (pintype "passive"))
      (node (ref "U3") (pin "35") (pinfunction "VSS_35") (pintype "passive"))
      (node (ref "U3") (pin "47") (pinfunction "VSS_47") (pintype "passive"))
      (node (ref "U3") (pin "8") (pinfunction "VSSA_8") (pintype "passive"))
      (node (ref "U4") (pin "10") (pinfunction "RESV9_1215_10") (pintype "passive"))
      (node (ref "U4") (pin "11") (pinfunction "RESV9_1215_11") (pintype "passive"))
      (node (ref "U4") (pin "12") (pinfunction "RESV9_1215_12") (pintype "passive"))
      (node (ref "U4") (pin "13") (pinfunction "GND_13") (pintype "passive"))
      (node (ref "U4") (pin "15") (pinfunction "RESV9_1215_15") (pintype "passive"))
      (node (ref "U4") (pin "9") (pinfunction "RESV9_1215_9") (pintype "passive"))
      (node (ref "U5") (pin "1") (pinfunction "GND/ADJ_1") (pintype "power_in"))
    )
    (net (code "33") (name "Net-(DS1-Pad1)") (class "Default")
      (node (ref "DS1") (pin "1") (pinfunction "1_1") (pintype "passive"))
      (node (ref "R3") (pin "1") (pinfunction "1_1") (pintype "passive"))
    )
    (net (code "34") (name "Net-(DS2-Pad1)") (class "Default")
      (node (ref "DS2") (pin "1") (pinfunction "1_1") (pintype "passive"))
      (node (ref "R6") (pin "2") (pinfunction "2_2") (pintype "passive"))
    )
    (net (code "35") (name "Net-(Q1-B)") (class "Default")
      (node (ref "Q1") (pin "1") (pinfunction "B_1") (pintype "passive"))
      (node (ref "R1") (pin "1") (pinfunction "1_1") (pintype "passive"))
    )
    (net (code "36") (name "Net-(Q1-C)") (class "Default")
      (node (ref "BZ1") (pin "2") (pinfunction "GND_2") (pintype "passive"))
      (node (ref "Q1") (pin "3") (pinfunction "C_3") (pintype "passive"))
    )
    (net (code "37") (name "Net-(U2-CAP)") (class "Default")
      (node (ref "C5") (pin "2") (pinfunction "2_2") (pintype "passive"))
      (node (ref "U2") (pin "9") (pinfunction "CAP_9") (pintype "passive"))
    )
    (net (code "38") (name "Net-(U2-XIN32)") (class "Default")
      (node (ref "C7") (pin "2") (pinfunction "2_2") (pintype "passive"))
      (node (ref "U2") (pin "27") (pinfunction "XIN32_27") (pintype "passive"))
      (node (ref "Y1") (pin "1") (pinfunction "1_1") (pintype "passive"))
    )
    (net (code "39") (name "Net-(U2-XOUT32{slash}CLKSEL1)") (class "Default")
      (node (ref "C6") (pin "2") (pinfunction "2_2") (pintype "passive"))
      (node (ref "U2") (pin "26") (pinfunction "XOUT32/CLKSEL1_26") (pintype "passive"))
      (node (ref "Y1") (pin "2") (pinfunction "2_2") (pintype "passive"))
    )
    (net (code "40") (name "Net-(U2-~{BOOT})") (class "Default")
      (node (ref "R2") (pin "1") (pinfunction "1_1") (pintype "passive"))
      (node (ref "U2") (pin "4") (pinfunction "~{BOOT}_4") (pintype "passive"))
    )
    (net (code "41") (name "Net-(U3-BOOT0)") (class "Default")
      (node (ref "R4") (pin "2") (pinfunction "2_2") (pintype "passive"))
      (node (ref "U3") (pin "44") (pinfunction "BOOT0_44") (pintype "passive"))
      (node (ref "s") (pin "2") (pinfunction "-_2") (pintype "passive"))
    )
    (net (code "42") (name "Net-(U3-NRST)") (class "Default")
      (node (ref "C12") (pin "2") (pinfunction "2_2") (pintype "passive"))
      (node (ref "R5") (pin "2") (pinfunction "2_2") (pintype "passive"))
      (node (ref "SW1") (pin "1") (pinfunction "1_1") (pintype "passive"))
      (node (ref "U3") (pin "7") (pinfunction "NRST_7") (pintype "passive"))
    )
    (net (code "43") (name "Net-(U3-PB2)") (class "Default")
      (node (ref "R7") (pin "2") (pinfunction "2_2") (pintype "passive"))
      (node (ref "U3") (pin "20") (pinfunction "PB2_20") (pintype "passive"))
    )
    (net (code "44") (name "Net-(U3-PH0-OSC_IN)") (class "Default")
      (node (ref "C9") (pin "2") (pinfunction "2_2") (pintype "passive"))
      (node (ref "U3") (pin "5") (pinfunction "PH0-OSC_IN_5") (pintype "passive"))
      (node (ref "Y2") (pin "2") (pinfunction "2_2") (pintype "passive"))
    )
    (net (code "45") (name "Net-(U3-PH1-OSC_OUT)") (class "Default")
      (node (ref "C14") (pin "2") (pinfunction "2_2") (pintype "passive"))
      (node (ref "U3") (pin "6") (pinfunction "PH1-OSC_OUT_6") (pintype "passive"))
      (node (ref "Y2") (pin "1") (pinfunction "1_1") (pintype "passive"))
    )
    (net (code "46") (name "Net-(U3-VCAP_1)") (class "Default")
      (node (ref "C10") (pin "2") (pinfunction "2_2") (pintype "passive"))
      (node (ref "U3") (pin "22") (pinfunction "VCAP_1_22") (pintype "passive"))
    )
    (net (code "47") (name "Net-(U4-REGOUT)") (class "Default")
      (node (ref "C8") (pin "1") (pinfunction "1_1") (pintype "passive"))
      (node (ref "U4") (pin "14") (pinfunction "REGOUT_14") (pintype "passive"))
    )
    (net (code "48") (name "unconnected-(J1-Pad5)") (class "Default")
      (node (ref "J1") (pin "5") (pinfunction "5_5") (pintype "passive"))
    )
    (net (code "49") (name "unconnected-(J2---Pad4)") (class "Default")
      (node (ref "J2") (pin "4") (pinfunction "-_4") (pintype "passive"))
    )
    (net (code "50") (name "unconnected-(J3---Pad4)") (class "Default")
      (node (ref "J3") (pin "4") (pinfunction "-_4") (pintype "passive"))
    )
    (net (code "51") (name "unconnected-(U2-ENV_SCL-Pad15)") (class "Default")
      (node (ref "U2") (pin "15") (pinfunction "ENV_SCL_15") (pintype "passive"))
    )
    (net (code "52") (name "unconnected-(U2-ENV_SDA-Pad16)") (class "Default")
      (node (ref "U2") (pin "16") (pinfunction "ENV_SDA_16") (pintype "passive"))
    )
    (net (code "53") (name "unconnected-(U3-EP-Pad49)") (class "Default")
      (node (ref "U3") (pin "49") (pinfunction "EP_49") (pintype "passive"))
    )
    (net (code "54") (name "unconnected-(U3-PA0-WKUP-Pad10)") (class "Default")
      (node (ref "U3") (pin "10") (pinfunction "PA0-WKUP_10") (pintype "passive"))
    )
    (net (code "55") (name "unconnected-(U3-PA1-Pad11)") (class "Default")
      (node (ref "U3") (pin "11") (pinfunction "PA1_11") (pintype "passive"))
    )
    (net (code "56") (name "unconnected-(U3-PA4-Pad14)") (class "Default")
      (node (ref "U3") (pin "14") (pinfunction "PA4_14") (pintype "passive"))
    )
    (net (code "57") (name "unconnected-(U3-PC15-OSC32_OUT-Pad4)") (class "Default")
      (node (ref "U3") (pin "4") (pinfunction "PC15-OSC32_OUT_4") (pintype "passive"))
    )
    (net (code "58") (name "unconnected-(U4-FSYNC-Pad8)") (class "Default")
      (node (ref "U4") (pin "8") (pinfunction "FSYNC_8") (pintype "passive"))
    )
    (net (code "59") (name "unconnected-(U4-RESV7-Pad7)") (class "Default")
      (node (ref "U4") (pin "7") (pinfunction "RESV7_7") (pintype "passive"))
    )
  )
)
